# LNA.net
KiCad netlist of a schematic drawn in Altium Designer
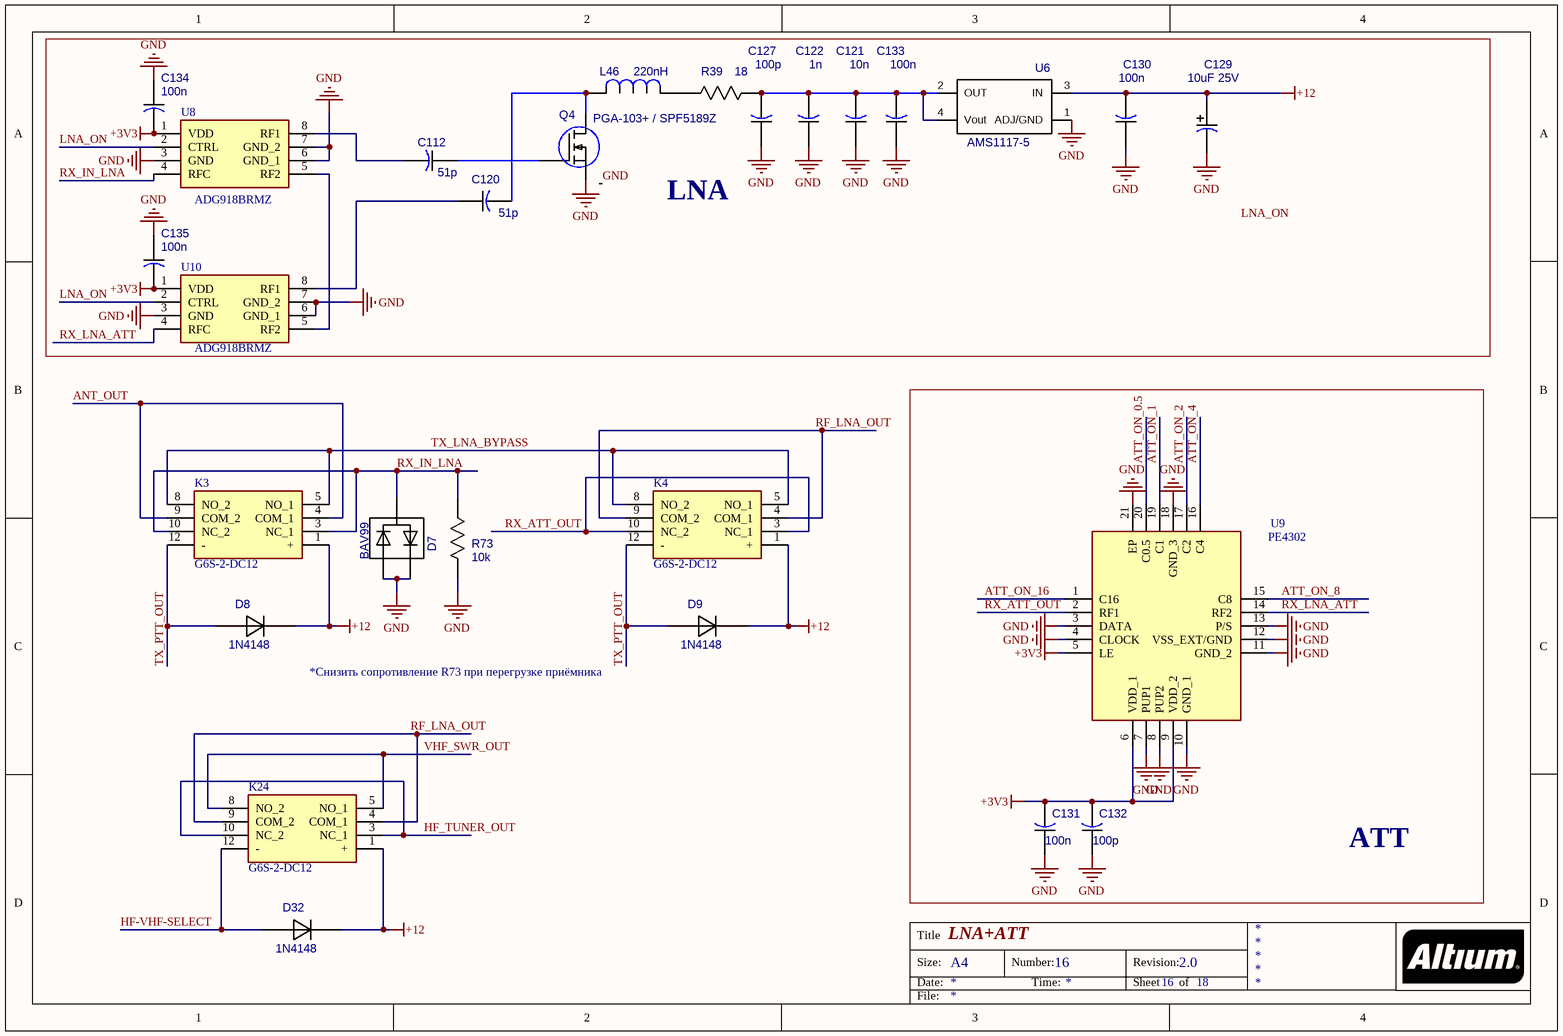
[diagram p0: LNA.SchDoc]

(export (version "E")
  (design (tool "Eeschema 10.0.6"))
  (components
    (comp (ref "C112")
      (value "51p")
      (footprint "CAP_0805")
      (description "CAP_0805")
      (libsource (lib "") (part "CAP_0805_1"))
    )
    (comp (ref "C120")
      (value "51p")
      (footprint "CAP_0805")
      (description "CAP_0805")
      (libsource (lib "") (part "CAP_0805_1"))
    )
    (comp (ref "C121")
      (value "10n")
      (footprint "6-0805_M")
      (description "CAP_0805")
      (libsource (lib "") (part "CAP_0805_1"))
    )
    (comp (ref "C122")
      (value "1n")
      (footprint "6-0805_M")
      (description "CAP_0805")
      (libsource (lib "") (part "CAP_0805_1"))
    )
    (comp (ref "C127")
      (value "100p")
      (footprint "6-0805_M")
      (description "CAP_0805")
      (libsource (lib "") (part "CAP_0805_1"))
    )
    (comp (ref "C129")
      (value "10uF 25V")
      (footprint "CAPAE_5.3x5.3h6.1")
      (description "CAPAE_5.3x5.3h6.1")
      (libsource (lib "*") (part "CAPAE_5.3x5.3h6.1"))
    )
    (comp (ref "C130")
      (value "100n")
      (footprint "CAP_0805")
      (description "CAP_0805")
      (libsource (lib "*") (part "CAP_0805"))
    )
    (comp (ref "C131")
      (value "100n")
      (footprint "6-0805_M")
      (description "CAP_0805")
      (libsource (lib "") (part "CAP_0805_1"))
    )
    (comp (ref "C132")
      (value "100p")
      (footprint "6-0805_M")
      (description "CAP_0805")
      (libsource (lib "") (part "CAP_0805_1"))
    )
    (comp (ref "C133")
      (value "100n")
      (footprint "CAP_0805")
      (description "CAP_0805")
      (libsource (lib "") (part "CAP_0805_1"))
    )
    (comp (ref "C134")
      (value "100n")
      (footprint "CAP_0805")
      (description "CAP_0805")
      (libsource (lib "") (part "CAP_0805_1"))
    )
    (comp (ref "C135")
      (value "100n")
      (footprint "CAP_0805")
      (description "CAP_0805")
      (libsource (lib "") (part "CAP_0805_1"))
    )
    (comp (ref "D7") (value "BAV99") (footprint "SOT23") (libsource (lib "*") (part "BAV99")))
    (comp (ref "D8") (value "1N4148") (footprint "SS14") (libsource (lib "RF-UNIT-BIG") (part "1N4148")))
    (comp (ref "D9") (value "1N4148") (footprint "SS14") (libsource (lib "RF-UNIT-BIG") (part "1N4148")))
    (comp (ref "D32") (value "1N4148") (footprint "SS14") (libsource (lib "RF-UNIT-BIG") (part "1N4148")))
    (comp (ref "K3")
      (value "G6S-2-DC12")
      (footprint "SamacSys:G6S2DC12")
      (description "Relay or Contactor")
      (fields (field (name "MOUSER PART NUMBER") "653-G6S-2-DC12A"))
      (libsource (lib "*") (part "G6S-2-DC12"))
    )
    (comp (ref "K4")
      (value "G6S-2-DC12")
      (footprint "SamacSys:G6S2DC12")
      (description "Relay or Contactor")
      (fields (field (name "MOUSER PART NUMBER") "653-G6S-2-DC12A"))
      (libsource (lib "*") (part "G6S-2-DC12"))
    )
    (comp (ref "K24")
      (value "G6S-2-DC12")
      (footprint "SamacSys:G6S2DC12")
      (description "Relay or Contactor")
      (fields (field (name "MOUSER PART NUMBER") "653-G6S-2-DC12A"))
      (libsource (lib "*") (part "G6S-2-DC12"))
    )
    (comp (ref "L46")
      (value "220nH")
      (footprint "IND_1206")
      (description "IND_1206")
      (libsource (lib "*") (part "IND_1206"))
    )
    (comp (ref "Q4")
      (value "PGA-103+ / SPF5189Z")
      (footprint "SOT89")
      (libsource (lib "*") (part "PGA-103+"))
    )
    (comp (ref "R39")
      (value "18")
      (footprint "RES_1206")
      (description "RES_1206")
      (libsource (lib "*") (part "RES_1206"))
    )
    (comp (ref "R73")
      (value "10k")
      (footprint "RES_1206")
      (description "RES_1206")
      (libsource (lib "*") (part "RES_1206"))
    )
    (comp (ref "U6") (value "AMS1117-5") (footprint "AMS1117-5") (libsource (lib "*") (part "AMS1117-5")))
    (comp (ref "U8")
      (value "ADG918BRMZ")
      (footprint "SOP65P490X110-8N")
      (description "Integrated Circuit")
      (fields (field (name "MOUSER PART NUMBER") "584-ADG918BRMZ") (field (name "RS PART NUMBER") "4969212P"))
      (libsource (lib "RF-UNIT-BIG") (part "ADG918BRMZ"))
    )
    (comp (ref "U9")
      (value "PE4302")
      (footprint "QFN50P400X400X90-21N")
      (description "Integrated Circuit")
      (fields (field (name "MANUFACTURER_PART_NUMBER") "PE4312C-Z"))
      (libsource (lib "RF-UNIT-BIG") (part "PE4312C-Z"))
    )
    (comp (ref "U10")
      (value "ADG918BRMZ")
      (footprint "SOP65P490X110-8N")
      (description "Integrated Circuit")
      (fields (field (name "MOUSER PART NUMBER") "584-ADG918BRMZ") (field (name "RS PART NUMBER") "4969212P"))
      (libsource (lib "RF-UNIT-BIG") (part "ADG918BRMZ"))
    )
  )
  (nets
    (net (code "1") (name "+3V3") (class "Default")
      (node (ref "C131") (pin "2") (pinfunction "2_2") (pintype "passive"))
      (node (ref "C132") (pin "2") (pinfunction "2_2") (pintype "passive"))
      (node (ref "C134") (pin "2") (pinfunction "2_2") (pintype "passive"))
      (node (ref "C135") (pin "2") (pinfunction "2_2") (pintype "passive"))
      (node (ref "U10") (pin "1") (pinfunction "VDD_1") (pintype "power_in"))
      (node (ref "U8") (pin "1") (pinfunction "VDD_1") (pintype "power_in"))
      (node (ref "U9") (pin "5") (pinfunction "LE_5") (pintype "passive"))
      (node (ref "U9") (pin "6") (pinfunction "VDD_1_6") (pintype "passive"))
      (node (ref "U9") (pin "9") (pinfunction "VDD_2_9") (pintype "passive"))
    )
    (net (code "2") (name "+12") (class "Default")
      (node (ref "C129") (pin "1") (pinfunction "PLUS_1") (pintype "passive"))
      (node (ref "C130") (pin "2") (pinfunction "2_2") (pintype "passive"))
      (node (ref "D32") (pin "1") (pinfunction "K_1") (pintype "passive"))
      (node (ref "D8") (pin "1") (pinfunction "K_1") (pintype "passive"))
      (node (ref "D9") (pin "1") (pinfunction "K_1") (pintype "passive"))
      (node (ref "K24") (pin "1") (pinfunction "+_1") (pintype "passive"))
      (node (ref "K3") (pin "1") (pinfunction "+_1") (pintype "passive"))
      (node (ref "K4") (pin "1") (pinfunction "+_1") (pintype "passive"))
      (node (ref "U6") (pin "3") (pinfunction "IN_3") (pintype "passive"))
    )
    (net (code "3") (name "/ANT_OUT") (class "Default")
      (node (ref "K3") (pin "4") (pinfunction "COM_1_4") (pintype "passive"))
      (node (ref "K3") (pin "9") (pinfunction "COM_2_9") (pintype "passive"))
    )
    (net (code "4") (name "/ATT_ON_0.5") (class "Default")
      (node (ref "U9") (pin "20") (pinfunction "C0.5_20") (pintype "passive"))
    )
    (net (code "5") (name "/ATT_ON_1") (class "Default")
      (node (ref "U9") (pin "19") (pinfunction "C1_19") (pintype "passive"))
    )
    (net (code "6") (name "/ATT_ON_2") (class "Default")
      (node (ref "U9") (pin "17") (pinfunction "C2_17") (pintype "passive"))
    )
    (net (code "7") (name "/ATT_ON_4") (class "Default")
      (node (ref "U9") (pin "16") (pinfunction "C4_16") (pintype "passive"))
    )
    (net (code "8") (name "/ATT_ON_8") (class "Default")
      (node (ref "U9") (pin "15") (pinfunction "C8_15") (pintype "passive"))
    )
    (net (code "9") (name "/ATT_ON_16") (class "Default")
      (node (ref "U9") (pin "1") (pinfunction "C16_1") (pintype "passive"))
    )
    (net (code "10") (name "/HF-VHF-SELECT") (class "Default")
      (node (ref "D32") (pin "2") (pinfunction "A_2") (pintype "passive"))
      (node (ref "K24") (pin "12") (pinfunction "-_12") (pintype "passive"))
    )
    (net (code "11") (name "/HF_TUNER_OUT") (class "Default")
      (node (ref "K24") (pin "10") (pinfunction "NC_2_10") (pintype "passive"))
      (node (ref "K24") (pin "3") (pinfunction "NC_1_3") (pintype "passive"))
    )
    (net (code "12") (name "/LNA_ON") (class "Default")
      (node (ref "U10") (pin "2") (pinfunction "CTRL_2") (pintype "passive"))
      (node (ref "U8") (pin "2") (pinfunction "CTRL_2") (pintype "passive"))
    )
    (net (code "13") (name "/RF_LNA_OUT") (class "Default")
      (node (ref "K24") (pin "4") (pinfunction "COM_1_4") (pintype "passive"))
      (node (ref "K24") (pin "9") (pinfunction "COM_2_9") (pintype "passive"))
      (node (ref "K4") (pin "4") (pinfunction "COM_1_4") (pintype "passive"))
      (node (ref "K4") (pin "9") (pinfunction "COM_2_9") (pintype "passive"))
    )
    (net (code "14") (name "/RX_ATT_OUT") (class "Default")
      (node (ref "K4") (pin "10") (pinfunction "NC_2_10") (pintype "passive"))
      (node (ref "K4") (pin "3") (pinfunction "NC_1_3") (pintype "passive"))
      (node (ref "U9") (pin "2") (pinfunction "RF1_2") (pintype "passive"))
    )
    (net (code "15") (name "/RX_IN_LNA") (class "Default")
      (node (ref "D7") (pin "3") (pinfunction "C(D1),A(D2)_3") (pintype "passive"))
      (node (ref "K3") (pin "10") (pinfunction "NC_2_10") (pintype "passive"))
      (node (ref "K3") (pin "3") (pinfunction "NC_1_3") (pintype "passive"))
      (node (ref "R73") (pin "2") (pinfunction "2_2") (pintype "passive"))
      (node (ref "U8") (pin "4") (pinfunction "RFC_4") (pintype "passive"))
    )
    (net (code "16") (name "/RX_LNA_ATT") (class "Default")
      (node (ref "U10") (pin "4") (pinfunction "RFC_4") (pintype "passive"))
      (node (ref "U9") (pin "14") (pinfunction "RF2_14") (pintype "passive"))
    )
    (net (code "17") (name "/TX_LNA_BYPASS") (class "Default")
      (node (ref "K3") (pin "5") (pinfunction "NO_1_5") (pintype "passive"))
      (node (ref "K3") (pin "8") (pinfunction "NO_2_8") (pintype "passive"))
      (node (ref "K4") (pin "5") (pinfunction "NO_1_5") (pintype "passive"))
      (node (ref "K4") (pin "8") (pinfunction "NO_2_8") (pintype "passive"))
    )
    (net (code "18") (name "/TX_PTT_OUT") (class "Default")
      (node (ref "D8") (pin "2") (pinfunction "A_2") (pintype "passive"))
      (node (ref "D9") (pin "2") (pinfunction "A_2") (pintype "passive"))
      (node (ref "K3") (pin "12") (pinfunction "-_12") (pintype "passive"))
      (node (ref "K4") (pin "12") (pinfunction "-_12") (pintype "passive"))
    )
    (net (code "19") (name "/VHF_SWR_OUT") (class "Default")
      (node (ref "K24") (pin "5") (pinfunction "NO_1_5") (pintype "passive"))
      (node (ref "K24") (pin "8") (pinfunction "NO_2_8") (pintype "passive"))
    )
    (net (code "20") (name "GND") (class "Default")
      (node (ref "C121") (pin "1") (pinfunction "1_1") (pintype "passive"))
      (node (ref "C122") (pin "1") (pinfunction "1_1") (pintype "passive"))
      (node (ref "C127") (pin "1") (pinfunction "1_1") (pintype "passive"))
      (node (ref "C129") (pin "2") (pinfunction "MINUS_2") (pintype "passive"))
      (node (ref "C130") (pin "1") (pinfunction "1_1") (pintype "passive"))
      (node (ref "C131") (pin "1") (pinfunction "1_1") (pintype "passive"))
      (node (ref "C132") (pin "1") (pinfunction "1_1") (pintype "passive"))
      (node (ref "C133") (pin "1") (pinfunction "1_1") (pintype "passive"))
      (node (ref "C134") (pin "1") (pinfunction "1_1") (pintype "passive"))
      (node (ref "C135") (pin "1") (pinfunction "1_1") (pintype "passive"))
      (node (ref "D7") (pin "1") (pinfunction "A(D1)_1") (pintype "passive"))
      (node (ref "D7") (pin "2") (pinfunction "C(D2)_2") (pintype "passive"))
      (node (ref "Q4") (pin "0") (pinfunction "0_0") (pintype "passive"))
      (node (ref "Q4") (pin "2") (pinfunction "S_2") (pintype "passive"))
      (node (ref "R73") (pin "1") (pinfunction "1_1") (pintype "passive"))
      (node (ref "U10") (pin "3") (pinfunction "GND_3") (pintype "power_in"))
      (node (ref "U10") (pin "6") (pinfunction "GND_1_6") (pintype "power_in"))
      (node (ref "U10") (pin "7") (pinfunction "GND_2_7") (pintype "power_in"))
      (node (ref "U6") (pin "1") (pinfunction "ADJ/GND_1") (pintype "passive"))
      (node (ref "U8") (pin "3") (pinfunction "GND_3") (pintype "power_in"))
      (node (ref "U8") (pin "6") (pinfunction "GND_1_6") (pintype "power_in"))
      (node (ref "U8") (pin "7") (pinfunction "GND_2_7") (pintype "power_in"))
      (node (ref "U9") (pin "10") (pinfunction "GND_1_10") (pintype "passive"))
      (node (ref "U9") (pin "11") (pinfunction "GND_2_11") (pintype "passive"))
      (node (ref "U9") (pin "12") (pinfunction "VSS_EXT/GND_12") (pintype "passive"))
      (node (ref "U9") (pin "13") (pinfunction "P/S_13") (pintype "passive"))
      (node (ref "U9") (pin "18") (pinfunction "GND_3_18") (pintype "passive"))
      (node (ref "U9") (pin "21") (pinfunction "EP_21") (pintype "passive"))
      (node (ref "U9") (pin "3") (pinfunction "DATA_3") (pintype "passive"))
      (node (ref "U9") (pin "4") (pinfunction "CLOCK_4") (pintype "passive"))
      (node (ref "U9") (pin "7") (pinfunction "PUP1_7") (pintype "passive"))
      (node (ref "U9") (pin "8") (pinfunction "PUP2_8") (pintype "passive"))
    )
    (net (code "21") (name "Net-(L46-1)") (class "Default")
      (node (ref "C120") (pin "2") (pinfunction "2_2") (pintype "passive"))
      (node (ref "L46") (pin "2") (pinfunction "1_2") (pintype "passive"))
      (node (ref "Q4") (pin "3") (pinfunction "D_3") (pintype "passive"))
    )
    (net (code "22") (name "Net-(L46-2)") (class "Default")
      (node (ref "L46") (pin "1") (pinfunction "2_1") (pintype "passive"))
      (node (ref "R39") (pin "2") (pinfunction "2_2") (pintype "passive"))
    )
    (net (code "23") (name "Net-(Q4-G)") (class "Default")
      (node (ref "C112") (pin "1") (pinfunction "1_1") (pintype "passive"))
      (node (ref "Q4") (pin "1") (pinfunction "G_1") (pintype "passive"))
    )
    (net (code "24") (name "Net-(U6-OUT)") (class "Default")
      (node (ref "C121") (pin "2") (pinfunction "2_2") (pintype "passive"))
      (node (ref "C122") (pin "2") (pinfunction "2_2") (pintype "passive"))
      (node (ref "C127") (pin "2") (pinfunction "2_2") (pintype "passive"))
      (node (ref "C133") (pin "2") (pinfunction "2_2") (pintype "passive"))
      (node (ref "R39") (pin "1") (pinfunction "1_1") (pintype "passive"))
      (node (ref "U6") (pin "2") (pinfunction "OUT_2") (pintype "passive"))
      (node (ref "U6") (pin "4") (pinfunction "Vout_4") (pintype "passive"))
    )
    (net (code "25") (name "Net-(U8-RF1)") (class "Default")
      (node (ref "C112") (pin "2") (pinfunction "2_2") (pintype "passive"))
      (node (ref "U8") (pin "8") (pinfunction "RF1_8") (pintype "passive"))
    )
    (net (code "26") (name "Net-(U10-RF1)") (class "Default")
      (node (ref "C120") (pin "1") (pinfunction "1_1") (pintype "passive"))
      (node (ref "U10") (pin "8") (pinfunction "RF1_8") (pintype "passive"))
    )
    (net (code "27") (name "Net-(U10-RF2)") (class "Default")
      (node (ref "U10") (pin "5") (pinfunction "RF2_5") (pintype "passive"))
      (node (ref "U8") (pin "5") (pinfunction "RF2_5") (pintype "passive"))
    )
  )
)
